# SecUSB.net
KiCad netlist of a schematic drawn in EAGLE
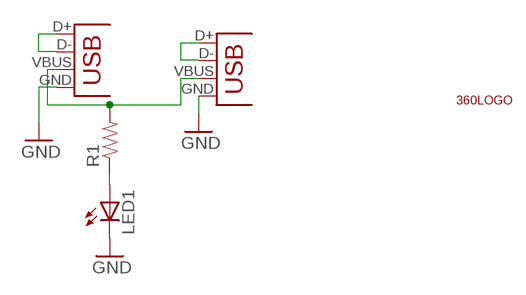
[diagram p0: schematic, sheet 1]

(export (version "E")
  (design (tool "Eeschema 10.0.6"))
  (components
    (comp (ref "LED1")
      (value "LED0603")
      (footprint "eagle-import:LED-0603")
      (libsource (lib "eagle-import") (part "LED0603"))
    )
    (comp (ref "R1")
      (value "RESISTOR0603-RES")
      (footprint "eagle-import:0603-RES")
      (libsource (lib "eagle-import") (part "RESISTOR0603-RES"))
    )
    (comp (ref "U$1")
      (value "360LOGO_0.8")
      (footprint "eagle-import:360LOGO_0.8")
      (libsource (lib "eagle-import") (part "360LOGO_0.8"))
    )
    (comp (ref "X2")
      (value "USB_4-A-H_2")
      (footprint "eagle-import:USB-A-H_2")
      (libsource (lib "eagle-import") (part "USB_4-A-H_2"))
    )
    (comp (ref "X3")
      (value "USB_4_3")
      (footprint "eagle-import:USB-A-3")
      (libsource (lib "eagle-import") (part "USB_4_3"))
    )
  )
  (nets
    (net (code "1") (name "GND") (class "Default")
      (node (ref "LED1") (pin "C") (pinfunction "C_C") (pintype "passive"))
      (node (ref "X2") (pin "GND") (pinfunction "GND_GND") (pintype "bidirectional"))
      (node (ref "X3") (pin "GND") (pinfunction "GND_GND") (pintype "bidirectional"))
    )
    (net (code "2") (name "Net-(LED1-PadA)") (class "Default")
      (node (ref "LED1") (pin "A") (pinfunction "A_A") (pintype "passive"))
      (node (ref "R1") (pin "1") (pinfunction "1_1") (pintype "passive"))
    )
    (net (code "3") (name "Net-(R1-Pad2)") (class "Default")
      (node (ref "R1") (pin "2") (pinfunction "2_2") (pintype "passive"))
      (node (ref "X2") (pin "VBUS") (pinfunction "VBUS_VBUS") (pintype "bidirectional"))
      (node (ref "X3") (pin "VBUS") (pinfunction "VBUS_VBUS") (pintype "bidirectional"))
    )
    (net (code "4") (name "Net-(X2-PadD+)") (class "Default")
      (node (ref "X2") (pin "D+") (pinfunction "D+_D+") (pintype "bidirectional"))
      (node (ref "X2") (pin "D-") (pinfunction "D-_D-") (pintype "bidirectional"))
    )
    (net (code "5") (name "Net-(X3-PadD+)") (class "Default")
      (node (ref "X3") (pin "D+") (pinfunction "D+_D+") (pintype "bidirectional"))
      (node (ref "X3") (pin "D-") (pinfunction "D-_D-") (pintype "bidirectional"))
    )
  )
)
